# power_supply.net
KiCad netlist of a schematic drawn in Altium Designer
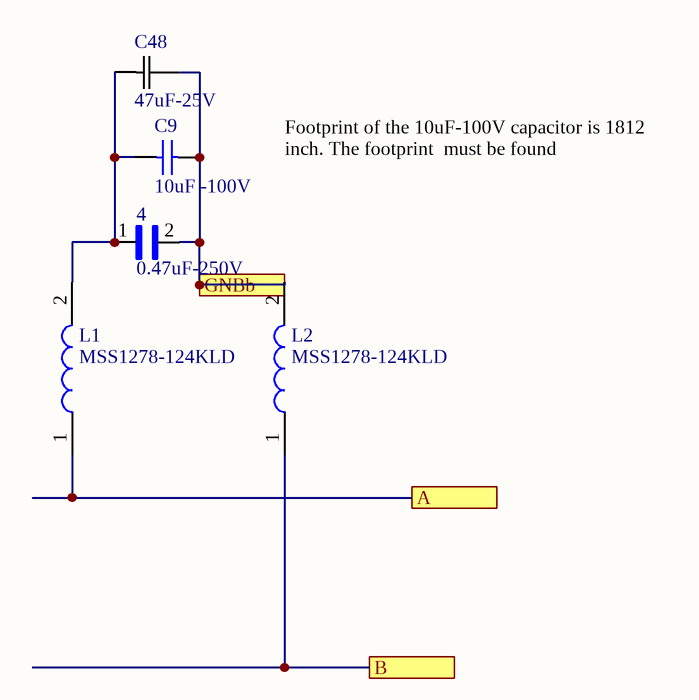
[diagram p0: power_supply.SchDoc]

(export (version "E")
  (design (tool "Eeschema 10.0.6"))
  (components
    (comp (ref "4")
      (value "0.47uF-250V")
      (footprint "CAPC3326X280N")
      (fields (field (name "MP") "C1210X474KARACAUTO") (field (name "MF") "{'manufacturer': u'KEMET'}"))
      (libsource (lib "GIGUL") (part "C1210X474KARACAUTO"))
    )
    (comp (ref "C9")
      (value "10uF -100V")
      (description "Capacitor")
      (fields (field (name "Comment") "Symbol"))
      (libsource (lib "GIGUL") (part "Symbol"))
    )
    (comp (ref "C48")
      (value "47uF-25V")
      (description "No Description Available")
      (fields
        (field (name "MANUFACTURER_PART_NUMBER") "GRM31CR61E476ME44K")
        (field (name "COPYRIGHT") "Copyright (C) 2021 Ultra Librarian. All rights reserved.")
      )
      (libsource (lib "GIGUL") (part "GRM31CR61E476ME44K"))
    )
    (comp (ref "L1")
      (value "MSS1278-124KLD")
      (footprint "INDPM120120X805N")
      (description "Inductor")
      (libsource (lib "GIGUL") (part "MSS1278-124KLD"))
    )
    (comp (ref "L2")
      (value "MSS1278-124KLD")
      (footprint "INDPM120120X805N")
      (description "Inductor")
      (libsource (lib "GIGUL") (part "MSS1278-124KLD"))
    )
  )
  (nets
    (net (code "1") (name "/A") (class "Default")
      (node (ref "L1") (pin "1") (pinfunction "1_1") (pintype "passive"))
    )
    (net (code "2") (name "/B") (class "Default")
      (node (ref "L2") (pin "1") (pinfunction "1_1") (pintype "passive"))
    )
    (net (code "3") (name "/GNBb") (class "Default")
      (node (ref "4") (pin "2") (pinfunction "2_2") (pintype "passive"))
      (node (ref "C48") (pin "2") (pinfunction "2_2") (pintype "passive"))
      (node (ref "C9") (pin "2") (pinfunction "2_2") (pintype "passive"))
      (node (ref "L2") (pin "2") (pinfunction "2_2") (pintype "passive"))
    )
    (net (code "4") (name "Net-(4-Pad1)") (class "Default")
      (node (ref "4") (pin "1") (pinfunction "1_1") (pintype "passive"))
      (node (ref "C48") (pin "1") (pinfunction "1_1") (pintype "passive"))
      (node (ref "C9") (pin "1") (pinfunction "1_1") (pintype "passive"))
      (node (ref "L1") (pin "2") (pinfunction "2_2") (pintype "passive"))
    )
  )
)
